# uz_frontpanel_main-mini.net
KiCad netlist of a schematic drawn in Altium Designer
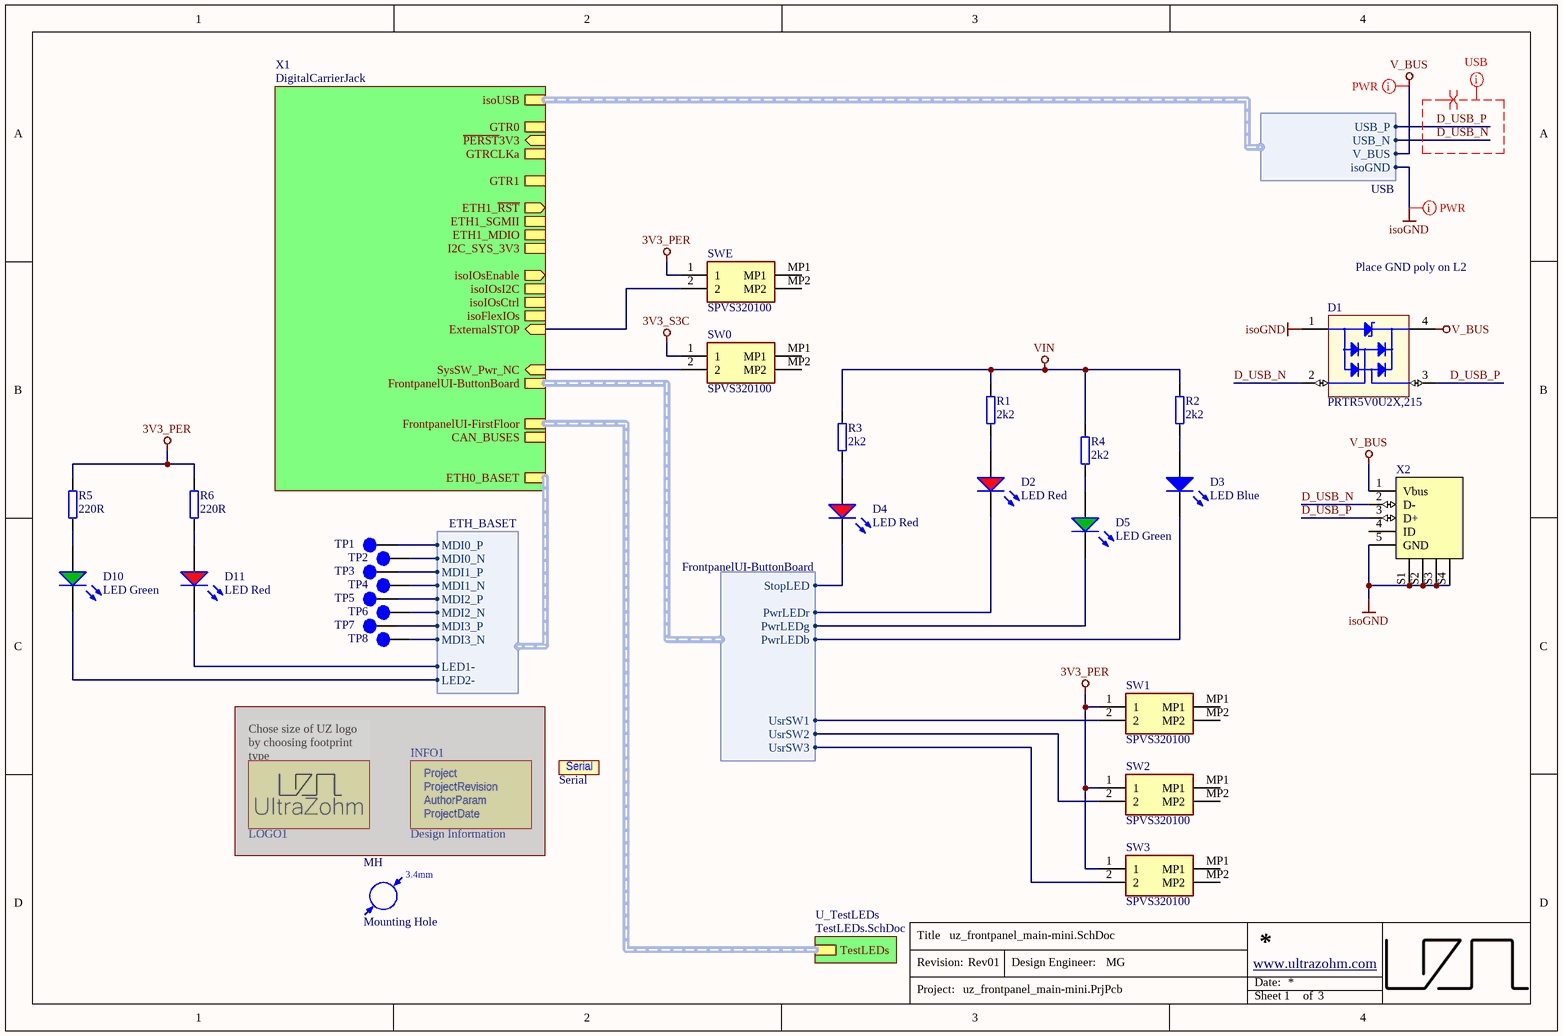
[diagram p0: uz_frontpanel_main-mini.SchDoc]

(export (version "E")
  (design (tool "Eeschema 10.0.6"))
  (components
    (comp (ref "D1")
      (value "PRTR5V0U2X,215")
      (footprint "SOT-143B-4")
      (description "ESD Suppressors / TVS Diodes PRTR5V0U2X/SOT143/SOT4")
      (fields
        (field (name "MANUFACTURER") "Nexperia")
        (field (name "LCSC PART NUMBER") "C12333")
        (field (name "CREATED FROM") "AGeiger")
      )
      (libsource (lib "user") (part "CD143A-SRxx"))
    )
    (comp (ref "D2")
      (value "LED Red")
      (footprint "WL-SMCW_0603")
      (description "Standard LEDs - SMD 0603 red")
      (fields
        (field (name "MANUFACTURER PART NUMBER") "UZgen_LED_0603_Red")
        (field (name "MANUFACTURER") "UZgen")
        (field (name "CREATED FROM") "UZgenTool")
      )
      (libsource (lib "user") (part "LED_Red"))
    )
    (comp (ref "D3")
      (value "LED Blue")
      (footprint "WL-SMCW_0603")
      (description "Standard LEDs - SMD 0603 blue")
      (fields
        (field (name "MANUFACTURER PART NUMBER") "UZgen_LED_0603_Blue")
        (field (name "MANUFACTURER") "UZgen")
        (field (name "CREATED FROM") "UZgenTool")
      )
      (libsource (lib "user") (part "LED_Blue"))
    )
    (comp (ref "D4")
      (value "LED Red")
      (footprint "WL-SMCW_0603")
      (description "Standard LEDs - SMD 0603 red")
      (fields
        (field (name "MANUFACTURER PART NUMBER") "UZgen_LED_0603_Red")
        (field (name "MANUFACTURER") "UZgen")
        (field (name "CREATED FROM") "UZgenTool")
      )
      (libsource (lib "user") (part "LED_Red"))
    )
    (comp (ref "D5")
      (value "LED Green")
      (footprint "WL-SMCW_0603")
      (description "Standard LEDs - SMD 0603 green")
      (fields
        (field (name "MANUFACTURER PART NUMBER") "UZgen_LED_0603_Green")
        (field (name "MANUFACTURER") "UZgen")
        (field (name "CREATED FROM") "UZgenTool")
      )
      (libsource (lib "user") (part "LED_Green"))
    )
    (comp (ref "D10")
      (value "LED Green")
      (footprint "WL-SMCW_0603")
      (description "Standard LEDs - SMD 0603 green")
      (fields
        (field (name "MANUFACTURER PART NUMBER") "UZgen_LED_0603_Green")
        (field (name "MANUFACTURER") "UZgen")
        (field (name "CREATED FROM") "UZgenTool")
      )
      (libsource (lib "user") (part "LED_Green"))
    )
    (comp (ref "D11")
      (value "LED Red")
      (footprint "WL-SMCW_0603")
      (description "Standard LEDs - SMD 0603 red")
      (fields
        (field (name "MANUFACTURER PART NUMBER") "UZgen_LED_0603_Red")
        (field (name "MANUFACTURER") "UZgen")
        (field (name "CREATED FROM") "UZgenTool")
      )
      (libsource (lib "user") (part "LED_Red"))
    )
    (comp (ref "INFO1")
      (value "Design Information")
      (footprint "Design_info")
      (fields (field (name "MANUFACTURER") "UltraZohm") (field (name "CREATED FROM") "MGremer"))
      (libsource (lib "user") (part "Design_info"))
    )
    (comp (ref "LOGO1")
      (value "UZ Logo")
      (footprint "UZ_Logo_tiny")
      (description "Official Project Logo of the UltraZohm")
      (fields
        (field (name "MANUFACTURER") "PCB Manufacturer")
        (field (name "MANUFACTURER PART NUMBER") "UltraZohm Logo")
        (field (name "CREATED FROM") "T. Wendt")
      )
      (libsource (lib "user") (part "UZ_LOGO"))
    )
    (comp (ref "MH")
      (value "Mounting Hole")
      (footprint "MH_3.4")
      (fields (field (name "CREATED FROM") "MHlatky"))
      (libsource (lib "user") (part "Mounting Hole"))
    )
    (comp (ref "R1")
      (value "2k2")
      (footprint "R_1206_TE")
      (description "Generic resistor")
      (fields
        (field (name "MANUFACTURER PART NUMBER") "UZgen_R_1206_2k2")
        (field (name "MANUFACTURER") "UZgen")
        (field (name "CREATED FROM") "UZgenTool")
      )
      (libsource (lib "user") (part "RES"))
    )
    (comp (ref "R2")
      (value "2k2")
      (footprint "R_1206_TE")
      (description "Generic resistor")
      (fields
        (field (name "MANUFACTURER PART NUMBER") "UZgen_R_1206_2k2")
        (field (name "MANUFACTURER") "UZgen")
        (field (name "CREATED FROM") "UZgenTool")
      )
      (libsource (lib "user") (part "RES"))
    )
    (comp (ref "R3")
      (value "2k2")
      (footprint "R_1206_TE")
      (description "Generic resistor")
      (fields
        (field (name "MANUFACTURER PART NUMBER") "UZgen_R_1206_2k2")
        (field (name "MANUFACTURER") "UZgen")
        (field (name "CREATED FROM") "UZgenTool")
      )
      (libsource (lib "user") (part "RES"))
    )
    (comp (ref "R4")
      (value "2k2")
      (footprint "R_1206_TE")
      (description "Generic resistor")
      (fields
        (field (name "MANUFACTURER PART NUMBER") "UZgen_R_1206_2k2")
        (field (name "MANUFACTURER") "UZgen")
        (field (name "CREATED FROM") "UZgenTool")
      )
      (libsource (lib "user") (part "RES"))
    )
    (comp (ref "R5")
      (value "220R")
      (footprint "R_0603_TE")
      (description "Generic resistor")
      (fields
        (field (name "MANUFACTURER PART NUMBER") "UZgen_R_0603_220R")
        (field (name "MANUFACTURER") "UZgen")
        (field (name "CREATED FROM") "UZgenTool")
      )
      (libsource (lib "user") (part "RES"))
    )
    (comp (ref "R6")
      (value "220R")
      (footprint "R_0603_TE")
      (description "Generic resistor")
      (fields
        (field (name "MANUFACTURER PART NUMBER") "UZgen_R_0603_220R")
        (field (name "MANUFACTURER") "UZgen")
        (field (name "CREATED FROM") "UZgenTool")
      )
      (libsource (lib "user") (part "RES"))
    )
    (comp (ref "Serial")
      (value "Serial #")
      (footprint "SERIAL")
      (description "Field to put in a serial number")
      (fields
        (field (name "MANUFACTURER") "PCB Manufacturer")
        (field (name "MANUFACTURER PART NUMBER") "Serial Number")
        (field (name "CREATED FROM") "T. Wendt")
      )
      (libsource (lib "user") (part "SerialNumber"))
    )
    (comp (ref "SW0")
      (value "SPVS320100")
      (footprint "SPVS320100")
      (description "Detector Switches 1 mAmp at 5 Volts 0.35 N")
      (fields
        (field (name "MANUFACTURER") "Alps Alpine")
        (field (name "LCSC PART NUMBER") "C160855")
        (field (name "CREATED FROM") "FRosner")
      )
      (libsource (lib "user") (part "SPVS320100"))
    )
    (comp (ref "SW1")
      (value "SPVS320100")
      (footprint "SPVS320100")
      (description "Detector Switches 1 mAmp at 5 Volts 0.35 N")
      (fields
        (field (name "MANUFACTURER") "Alps Alpine")
        (field (name "LCSC PART NUMBER") "C160855")
        (field (name "CREATED FROM") "FRosner")
      )
      (libsource (lib "user") (part "SPVS320100"))
    )
    (comp (ref "SW2")
      (value "SPVS320100")
      (footprint "SPVS320100")
      (description "Detector Switches 1 mAmp at 5 Volts 0.35 N")
      (fields
        (field (name "MANUFACTURER") "Alps Alpine")
        (field (name "LCSC PART NUMBER") "C160855")
        (field (name "CREATED FROM") "FRosner")
      )
      (libsource (lib "user") (part "SPVS320100"))
    )
    (comp (ref "SW3")
      (value "SPVS320100")
      (footprint "SPVS320100")
      (description "Detector Switches 1 mAmp at 5 Volts 0.35 N")
      (fields
        (field (name "MANUFACTURER") "Alps Alpine")
        (field (name "LCSC PART NUMBER") "C160855")
        (field (name "CREATED FROM") "FRosner")
      )
      (libsource (lib "user") (part "SPVS320100"))
    )
    (comp (ref "SWE")
      (value "SPVS320100")
      (footprint "SPVS320100")
      (description "Detector Switches 1 mAmp at 5 Volts 0.35 N")
      (fields
        (field (name "MANUFACTURER") "Alps Alpine")
        (field (name "LCSC PART NUMBER") "C160855")
        (field (name "CREATED FROM") "FRosner")
      )
      (libsource (lib "user") (part "SPVS320100"))
    )
    (comp (ref "TP1")
      (value "Testpoint 1mm")
      (footprint "TP_1mm")
      (fields
        (field (name "MANUFACTURER PART NUMBER") "NULL")
        (field (name "CREATED") "2018_06_25_AGeiger")
        (field (name "CREATED FROM") "AGeiger")
      )
      (libsource (lib "user") (part "TP_1mm"))
    )
    (comp (ref "TP2")
      (value "Testpoint 1mm")
      (footprint "TP_1mm")
      (fields
        (field (name "MANUFACTURER PART NUMBER") "NULL")
        (field (name "CREATED") "2018_06_25_AGeiger")
        (field (name "CREATED FROM") "AGeiger")
      )
      (libsource (lib "user") (part "TP_1mm"))
    )
    (comp (ref "TP3")
      (value "Testpoint 1mm")
      (footprint "TP_1mm")
      (fields
        (field (name "MANUFACTURER PART NUMBER") "NULL")
        (field (name "CREATED") "2018_06_25_AGeiger")
        (field (name "CREATED FROM") "AGeiger")
      )
      (libsource (lib "user") (part "TP_1mm"))
    )
    (comp (ref "TP4")
      (value "Testpoint 1mm")
      (footprint "TP_1mm")
      (fields
        (field (name "MANUFACTURER PART NUMBER") "NULL")
        (field (name "CREATED") "2018_06_25_AGeiger")
        (field (name "CREATED FROM") "AGeiger")
      )
      (libsource (lib "user") (part "TP_1mm"))
    )
    (comp (ref "TP5")
      (value "Testpoint 1mm")
      (footprint "TP_1mm")
      (fields
        (field (name "MANUFACTURER PART NUMBER") "NULL")
        (field (name "CREATED") "2018_06_25_AGeiger")
        (field (name "CREATED FROM") "AGeiger")
      )
      (libsource (lib "user") (part "TP_1mm"))
    )
    (comp (ref "TP6")
      (value "Testpoint 1mm")
      (footprint "TP_1mm")
      (fields
        (field (name "MANUFACTURER PART NUMBER") "NULL")
        (field (name "CREATED") "2018_06_25_AGeiger")
        (field (name "CREATED FROM") "AGeiger")
      )
      (libsource (lib "user") (part "TP_1mm"))
    )
    (comp (ref "TP7")
      (value "Testpoint 1mm")
      (footprint "TP_1mm")
      (fields
        (field (name "MANUFACTURER PART NUMBER") "NULL")
        (field (name "CREATED") "2018_06_25_AGeiger")
        (field (name "CREATED FROM") "AGeiger")
      )
      (libsource (lib "user") (part "TP_1mm"))
    )
    (comp (ref "TP8")
      (value "Testpoint 1mm")
      (footprint "TP_1mm")
      (fields
        (field (name "MANUFACTURER PART NUMBER") "NULL")
        (field (name "CREATED") "2018_06_25_AGeiger")
        (field (name "CREATED FROM") "AGeiger")
      )
      (libsource (lib "user") (part "TP_1mm"))
    )
    (comp (ref "X2")
      (value "Mini USB")
      (footprint "MINI_USB_5S_B _TYPE")
      (description "1A 1 Surface Mount 5P Female -30℃~+80℃ SMD USB Connectors ROHS")
      (fields
        (field (name "MANUFACTURER PART NUMBER") "MINI 5PTP")
        (field (name "MANUFACTURER") "SHOU HAN")
        (field (name "CREATED FROM") "AGeiger")
      )
      (libsource (lib "user") (part "Mini_USB"))
    )
  )
  (nets
    (net (code "5") (name "/D_USB_N") (class "Default")
      (node (ref "D1") (pin "2") (pinfunction "I/O_2") (pintype "bidirectional"))
      (node (ref "X2") (pin "2") (pinfunction "D-_2") (pintype "bidirectional"))
    )
    (net (code "6") (name "/D_USB_P") (class "Default")
      (node (ref "D1") (pin "3") (pinfunction "I/O_3") (pintype "bidirectional"))
      (node (ref "X2") (pin "3") (pinfunction "D+_3") (pintype "bidirectional"))
    )
    (net (code "10") (name "/ExternalSTOP") (class "Default")
      (node (ref "SWE") (pin "2") (pinfunction "2_2") (pintype "passive"))
    )
    (net (code "16") (name "/LED1-") (class "Default")
      (node (ref "D11") (pin "1") (pinfunction "K_1") (pintype "passive"))
    )
    (net (code "17") (name "/LED2-") (class "Default")
      (node (ref "D10") (pin "1") (pinfunction "K_1") (pintype "passive"))
    )
    (net (code "18") (name "/MDI0_N") (class "Default") (node (ref "TP2") (pin "1") (pintype "passive")))
    (net (code "19") (name "/MDI0_P") (class "Default") (node (ref "TP1") (pin "1") (pintype "passive")))
    (net (code "20") (name "/MDI1_N") (class "Default") (node (ref "TP4") (pin "1") (pintype "passive")))
    (net (code "21") (name "/MDI1_P") (class "Default") (node (ref "TP3") (pin "1") (pintype "passive")))
    (net (code "22") (name "/MDI2_N") (class "Default") (node (ref "TP6") (pin "1") (pintype "passive")))
    (net (code "23") (name "/MDI2_P") (class "Default") (node (ref "TP5") (pin "1") (pintype "passive")))
    (net (code "24") (name "/MDI3_N") (class "Default") (node (ref "TP8") (pin "1") (pintype "passive")))
    (net (code "25") (name "/MDI3_P") (class "Default") (node (ref "TP7") (pin "1") (pintype "passive")))
    (net (code "26") (name "/PwrLEDb") (class "Default")
      (node (ref "D3") (pin "1") (pinfunction "K_1") (pintype "passive"))
    )
    (net (code "27") (name "/PwrLEDg") (class "Default")
      (node (ref "D5") (pin "1") (pinfunction "K_1") (pintype "passive"))
    )
    (net (code "28") (name "/PwrLEDr") (class "Default")
      (node (ref "D2") (pin "1") (pinfunction "K_1") (pintype "passive"))
    )
    (net (code "29") (name "/StopLED") (class "Default")
      (node (ref "D4") (pin "1") (pinfunction "K_1") (pintype "passive"))
    )
    (net (code "30") (name "/SysSW_Pwr_NC") (class "Default")
      (node (ref "SW0") (pin "2") (pinfunction "2_2") (pintype "passive"))
    )
    (net (code "31") (name "/UsrSW1") (class "Default")
      (node (ref "SW1") (pin "2") (pinfunction "2_2") (pintype "passive"))
    )
    (net (code "32") (name "/UsrSW2") (class "Default")
      (node (ref "SW2") (pin "2") (pinfunction "2_2") (pintype "passive"))
    )
    (net (code "33") (name "/UsrSW3") (class "Default")
      (node (ref "SW3") (pin "2") (pinfunction "2_2") (pintype "passive"))
    )
    (net (code "42") (name "3V3_PER") (class "Default")
      (node (ref "R5") (pin "2") (pinfunction "2_2") (pintype "passive"))
      (node (ref "R6") (pin "2") (pinfunction "2_2") (pintype "passive"))
      (node (ref "SW1") (pin "1") (pinfunction "1_1") (pintype "passive"))
      (node (ref "SW2") (pin "1") (pinfunction "1_1") (pintype "passive"))
      (node (ref "SW3") (pin "1") (pinfunction "1_1") (pintype "passive"))
      (node (ref "SWE") (pin "1") (pinfunction "1_1") (pintype "passive"))
    )
    (net (code "43") (name "3V3_S3C") (class "Default")
      (node (ref "SW0") (pin "1") (pinfunction "1_1") (pintype "passive"))
    )
    (net (code "44") (name "Net-(D2-A)") (class "Default")
      (node (ref "D2") (pin "2") (pinfunction "A_2") (pintype "passive"))
      (node (ref "R1") (pin "1") (pinfunction "1_1") (pintype "passive"))
    )
    (net (code "45") (name "Net-(D3-A)") (class "Default")
      (node (ref "D3") (pin "2") (pinfunction "A_2") (pintype "passive"))
      (node (ref "R2") (pin "1") (pinfunction "1_1") (pintype "passive"))
    )
    (net (code "46") (name "Net-(D4-A)") (class "Default")
      (node (ref "D4") (pin "2") (pinfunction "A_2") (pintype "passive"))
      (node (ref "R3") (pin "1") (pinfunction "1_1") (pintype "passive"))
    )
    (net (code "47") (name "Net-(D5-A)") (class "Default")
      (node (ref "D5") (pin "2") (pinfunction "A_2") (pintype "passive"))
      (node (ref "R4") (pin "1") (pinfunction "1_1") (pintype "passive"))
    )
    (net (code "48") (name "Net-(D10-A)") (class "Default")
      (node (ref "D10") (pin "2") (pinfunction "A_2") (pintype "passive"))
      (node (ref "R5") (pin "1") (pinfunction "1_1") (pintype "passive"))
    )
    (net (code "49") (name "Net-(D11-A)") (class "Default")
      (node (ref "D11") (pin "2") (pinfunction "A_2") (pintype "passive"))
      (node (ref "R6") (pin "1") (pinfunction "1_1") (pintype "passive"))
    )
    (net (code "50") (name "VIN") (class "Default")
      (node (ref "R1") (pin "2") (pinfunction "2_2") (pintype "passive"))
      (node (ref "R2") (pin "2") (pinfunction "2_2") (pintype "passive"))
      (node (ref "R3") (pin "2") (pinfunction "2_2") (pintype "passive"))
      (node (ref "R4") (pin "2") (pinfunction "2_2") (pintype "passive"))
    )
    (net (code "51") (name "V_BUS") (class "Default")
      (node (ref "D1") (pin "4") (pinfunction "REF_4") (pintype "passive"))
      (node (ref "X2") (pin "1") (pinfunction "Vbus_1") (pintype "power_in"))
    )
    (net (code "52") (name "isoGND") (class "Default")
      (node (ref "D1") (pin "1") (pinfunction "GND_1") (pintype "passive"))
      (node (ref "X2") (pin "5") (pinfunction "GND_5") (pintype "power_in"))
      (node (ref "X2") (pin "S1") (pinfunction "S1_S1") (pintype "passive"))
      (node (ref "X2") (pin "S2") (pinfunction "S2_S2") (pintype "passive"))
      (node (ref "X2") (pin "S3") (pinfunction "S3_S3") (pintype "passive"))
      (node (ref "X2") (pin "S4") (pinfunction "S4_S4") (pintype "passive"))
    )
    (net (code "53") (name "unconnected-(SW0-PadMP1)") (class "Default")
      (node (ref "SW0") (pin "MP1") (pinfunction "MP1_MP1") (pintype "passive"))
    )
    (net (code "54") (name "unconnected-(SW0-PadMP2)") (class "Default")
      (node (ref "SW0") (pin "MP2") (pinfunction "MP2_MP2") (pintype "passive"))
    )
    (net (code "55") (name "unconnected-(SW1-PadMP1)") (class "Default")
      (node (ref "SW1") (pin "MP1") (pinfunction "MP1_MP1") (pintype "passive"))
    )
    (net (code "56") (name "unconnected-(SW1-PadMP2)") (class "Default")
      (node (ref "SW1") (pin "MP2") (pinfunction "MP2_MP2") (pintype "passive"))
    )
    (net (code "57") (name "unconnected-(SW2-PadMP1)") (class "Default")
      (node (ref "SW2") (pin "MP1") (pinfunction "MP1_MP1") (pintype "passive"))
    )
    (net (code "58") (name "unconnected-(SW2-PadMP2)") (class "Default")
      (node (ref "SW2") (pin "MP2") (pinfunction "MP2_MP2") (pintype "passive"))
    )
    (net (code "59") (name "unconnected-(SW3-PadMP1)") (class "Default")
      (node (ref "SW3") (pin "MP1") (pinfunction "MP1_MP1") (pintype "passive"))
    )
    (net (code "60") (name "unconnected-(SW3-PadMP2)") (class "Default")
      (node (ref "SW3") (pin "MP2") (pinfunction "MP2_MP2") (pintype "passive"))
    )
    (net (code "61") (name "unconnected-(SWE-PadMP1)") (class "Default")
      (node (ref "SWE") (pin "MP1") (pinfunction "MP1_MP1") (pintype "passive"))
    )
    (net (code "62") (name "unconnected-(SWE-PadMP2)") (class "Default")
      (node (ref "SWE") (pin "MP2") (pinfunction "MP2_MP2") (pintype "passive"))
    )
    (net (code "63") (name "unconnected-(X2-ID-Pad4)") (class "Default")
      (node (ref "X2") (pin "4") (pinfunction "ID_4") (pintype "passive"))
    )
  )
)
